# SparkFun_ACS712LowCurrentSensorBoardv14.net
KiCad netlist of a schematic drawn in EAGLE
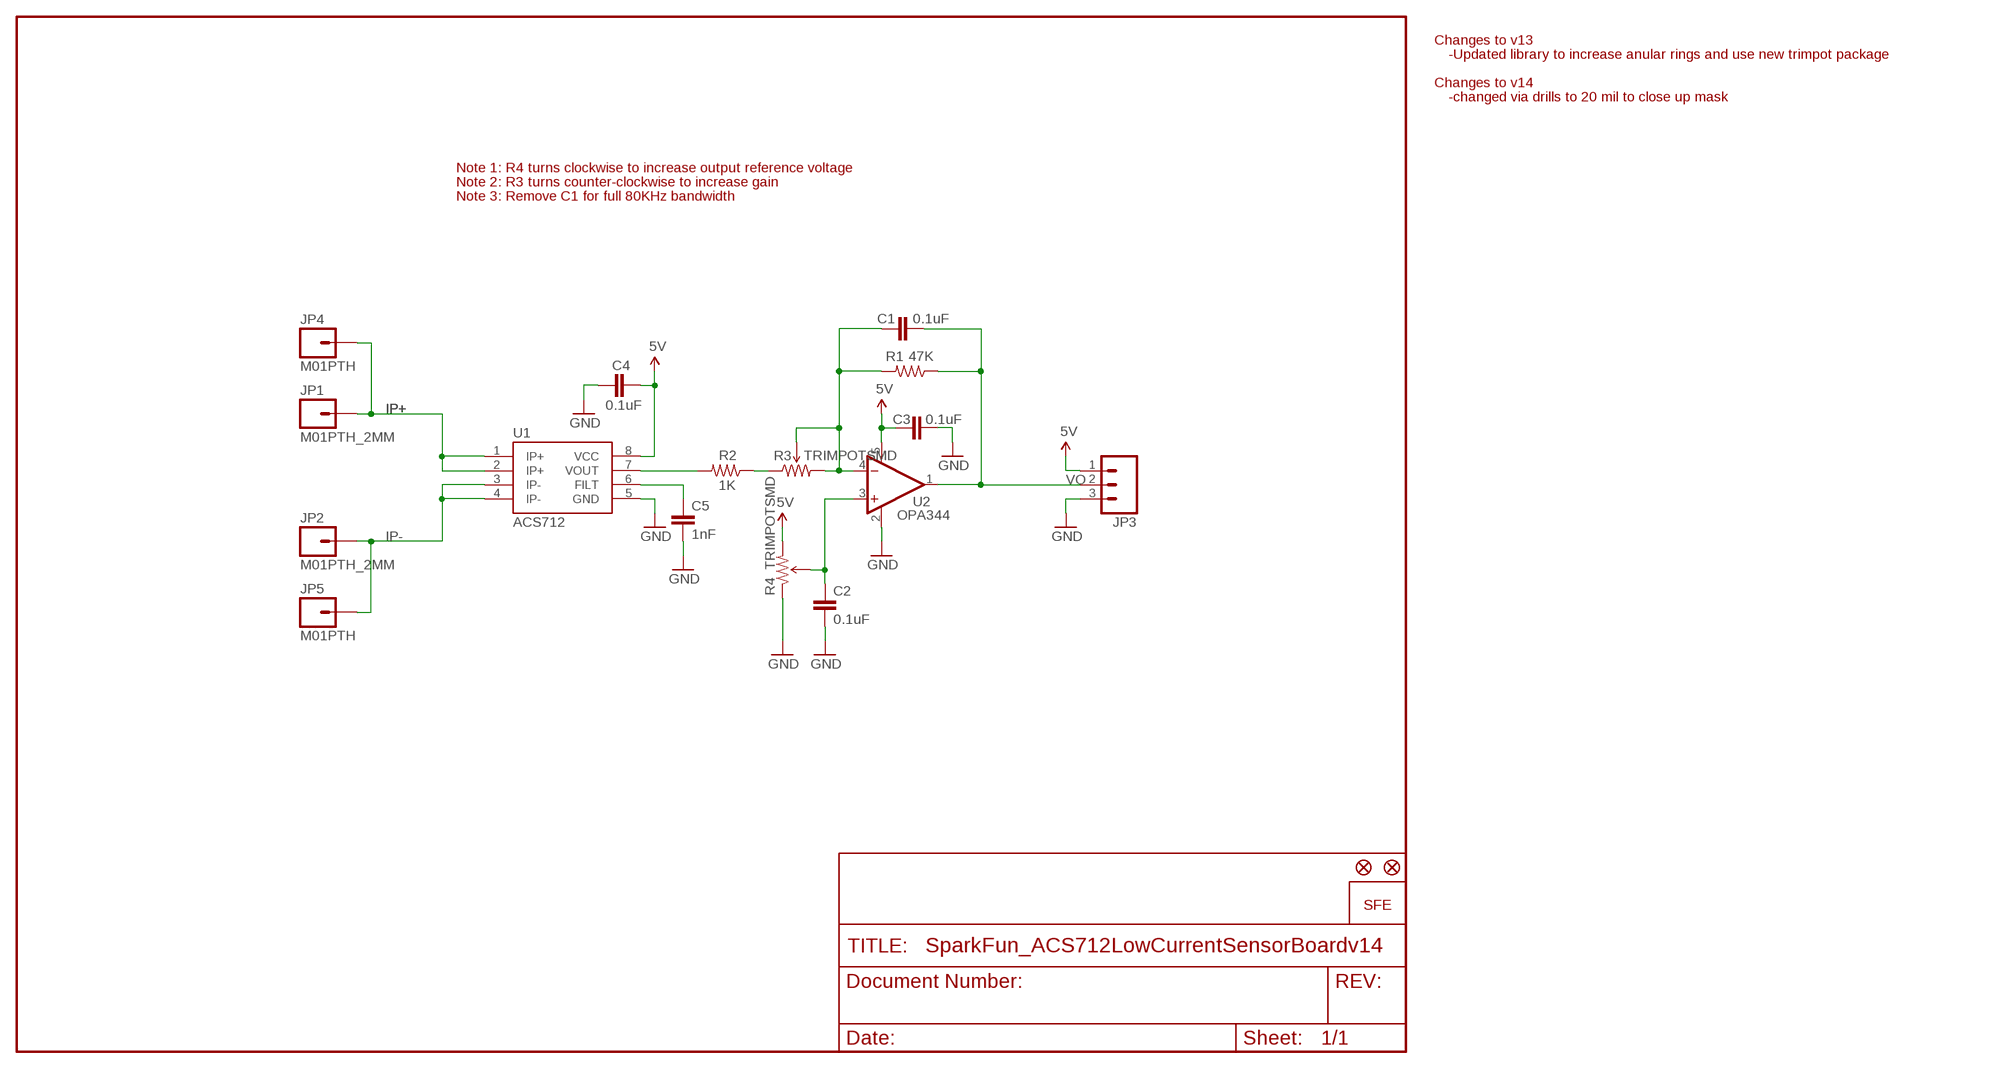
[diagram p0: schematic, sheet 1]

(export (version "E")
  (design (tool "Eeschema 10.0.6"))
  (components
    (comp (ref "C1")
      (value "0.1uF")
      (footprint "eagle-import:0402-CAP")
      (libsource (lib "eagle-import") (part "CAP0402-CAP"))
    )
    (comp (ref "C2")
      (value "0.1uF")
      (footprint "eagle-import:0402-CAP")
      (libsource (lib "eagle-import") (part "CAP0402-CAP"))
    )
    (comp (ref "C3")
      (value "0.1uF")
      (footprint "eagle-import:0402-CAP")
      (libsource (lib "eagle-import") (part "CAP0402-CAP"))
    )
    (comp (ref "C4")
      (value "0.1uF")
      (footprint "eagle-import:0402-CAP")
      (libsource (lib "eagle-import") (part "CAP0402-CAP"))
    )
    (comp (ref "C5")
      (value "1nF")
      (footprint "eagle-import:0402-CAP")
      (libsource (lib "eagle-import") (part "CAP0402-CAP"))
    )
    (comp (ref "JP1")
      (value "M01PTH_2MM")
      (footprint "eagle-import:1X01_2MM")
      (libsource (lib "eagle-import") (part "M01PTH_2MM"))
    )
    (comp (ref "JP2")
      (value "M01PTH_2MM")
      (footprint "eagle-import:1X01_2MM")
      (libsource (lib "eagle-import") (part "M01PTH_2MM"))
    )
    (comp (ref "JP3")
      (value "M03PTH")
      (footprint "eagle-import:1X03")
      (libsource (lib "eagle-import") (part "M03PTH"))
    )
    (comp (ref "JP4")
      (value "M01PTH")
      (footprint "eagle-import:1X01")
      (libsource (lib "eagle-import") (part "M01PTH"))
    )
    (comp (ref "JP5")
      (value "M01PTH")
      (footprint "eagle-import:1X01")
      (libsource (lib "eagle-import") (part "M01PTH"))
    )
    (comp (ref "R1")
      (value "47K")
      (footprint "eagle-import:0402-RES")
      (libsource (lib "eagle-import") (part "RESISTOR0402-RES"))
    )
    (comp (ref "R2")
      (value "1K")
      (footprint "eagle-import:0402-RES")
      (libsource (lib "eagle-import") (part "RESISTOR0402-RES"))
    )
    (comp (ref "R3")
      (value "TRIMPOTSMD")
      (footprint "eagle-import:TRIMPOT-3MM")
      (libsource (lib "eagle-import") (part "TRIMPOTSMD"))
    )
    (comp (ref "R4")
      (value "TRIMPOTSMD")
      (footprint "eagle-import:TRIMPOT-3MM")
      (libsource (lib "eagle-import") (part "TRIMPOTSMD"))
    )
    (comp (ref "U$1")
      (value "FIDUCIALUFIDUCIAL")
      (footprint "eagle-import:MICRO-FIDUCIAL")
      (libsource (lib "eagle-import") (part "FIDUCIALUFIDUCIAL"))
    )
    (comp (ref "U$2")
      (value "LOGO-SFENEW")
      (footprint "eagle-import:SFE-NEW-WEBLOGO")
      (libsource (lib "eagle-import") (part "LOGO-SFENEW"))
    )
    (comp (ref "U$3")
      (value "FIDUCIALUFIDUCIAL")
      (footprint "eagle-import:MICRO-FIDUCIAL")
      (libsource (lib "eagle-import") (part "FIDUCIALUFIDUCIAL"))
    )
    (comp (ref "U1")
      (value "ACS712")
      (footprint "eagle-import:SO08")
      (libsource (lib "eagle-import") (part "ACS712"))
    )
    (comp (ref "U2")
      (value "OPA344")
      (footprint "eagle-import:SOT23-5")
      (libsource (lib "eagle-import") (part "OPA344"))
    )
  )
  (nets
    (net (code "1") (name "/IP+") (class "Default")
      (node (ref "JP1") (pin "1") (pinfunction "1_1") (pintype "passive"))
      (node (ref "JP4") (pin "1") (pinfunction "1_1") (pintype "passive"))
      (node (ref "U1") (pin "1") (pinfunction "IP+_1") (pintype "bidirectional"))
      (node (ref "U1") (pin "2") (pinfunction "IP+_2") (pintype "bidirectional"))
    )
    (net (code "2") (name "/IP-") (class "Default")
      (node (ref "JP2") (pin "1") (pinfunction "1_1") (pintype "passive"))
      (node (ref "JP5") (pin "1") (pinfunction "1_1") (pintype "passive"))
      (node (ref "U1") (pin "3") (pinfunction "IP-_3") (pintype "bidirectional"))
      (node (ref "U1") (pin "4") (pinfunction "IP-_4") (pintype "bidirectional"))
    )
    (net (code "3") (name "/VO") (class "Default")
      (node (ref "C1") (pin "1") (pinfunction "1_1") (pintype "passive"))
      (node (ref "JP3") (pin "2") (pinfunction "2_2") (pintype "passive"))
      (node (ref "R1") (pin "1") (pinfunction "1_1") (pintype "passive"))
      (node (ref "U2") (pin "1") (pinfunction "OUT_1") (pintype "output"))
    )
    (net (code "4") (name "5V") (class "Default")
      (node (ref "C3") (pin "1") (pinfunction "1_1") (pintype "passive"))
      (node (ref "C4") (pin "2") (pinfunction "2_2") (pintype "passive"))
      (node (ref "JP3") (pin "1") (pinfunction "1_1") (pintype "passive"))
      (node (ref "R4") (pin "3") (pinfunction "CW_3") (pintype "passive"))
      (node (ref "U1") (pin "8") (pinfunction "VCC_8") (pintype "bidirectional"))
      (node (ref "U2") (pin "5") (pinfunction "V+_5") (pintype "power_in"))
    )
    (net (code "5") (name "GND") (class "Default")
      (node (ref "C2") (pin "2") (pinfunction "2_2") (pintype "passive"))
      (node (ref "C3") (pin "2") (pinfunction "2_2") (pintype "passive"))
      (node (ref "C4") (pin "1") (pinfunction "1_1") (pintype "passive"))
      (node (ref "C5") (pin "2") (pinfunction "2_2") (pintype "passive"))
      (node (ref "JP3") (pin "3") (pinfunction "3_3") (pintype "passive"))
      (node (ref "R4") (pin "1") (pinfunction "CCW_1") (pintype "passive"))
      (node (ref "U1") (pin "5") (pinfunction "GND_5") (pintype "bidirectional"))
      (node (ref "U2") (pin "2") (pinfunction "V-_2") (pintype "power_in"))
    )
    (net (code "6") (name "Net-(R3-CCW)") (class "Default")
      (node (ref "R2") (pin "1") (pinfunction "1_1") (pintype "passive"))
      (node (ref "R3") (pin "1") (pinfunction "CCW_1") (pintype "passive"))
    )
    (net (code "7") (name "Net-(R3-CW)") (class "Default")
      (node (ref "C1") (pin "2") (pinfunction "2_2") (pintype "passive"))
      (node (ref "R1") (pin "2") (pinfunction "2_2") (pintype "passive"))
      (node (ref "R3") (pin "2") (pinfunction "WIPER_2") (pintype "passive"))
      (node (ref "R3") (pin "3") (pinfunction "CW_3") (pintype "passive"))
      (node (ref "U2") (pin "4") (pinfunction "-IN_4") (pintype "input"))
    )
    (net (code "8") (name "Net-(R4-WIPER)") (class "Default")
      (node (ref "C2") (pin "1") (pinfunction "1_1") (pintype "passive"))
      (node (ref "R4") (pin "2") (pinfunction "WIPER_2") (pintype "passive"))
      (node (ref "U2") (pin "3") (pinfunction "+IN_3") (pintype "input"))
    )
    (net (code "9") (name "Net-(U1-FILT)") (class "Default")
      (node (ref "C5") (pin "1") (pinfunction "1_1") (pintype "passive"))
      (node (ref "U1") (pin "6") (pinfunction "FILT_6") (pintype "bidirectional"))
    )
    (net (code "10") (name "Net-(U1-VOUT)") (class "Default")
      (node (ref "R2") (pin "2") (pinfunction "2_2") (pintype "passive"))
      (node (ref "U1") (pin "7") (pinfunction "VOUT_7") (pintype "bidirectional"))
    )
  )
)
